# MSXIV_DC-DC_Converter.net
KiCad netlist of a schematic drawn in Altium Designer
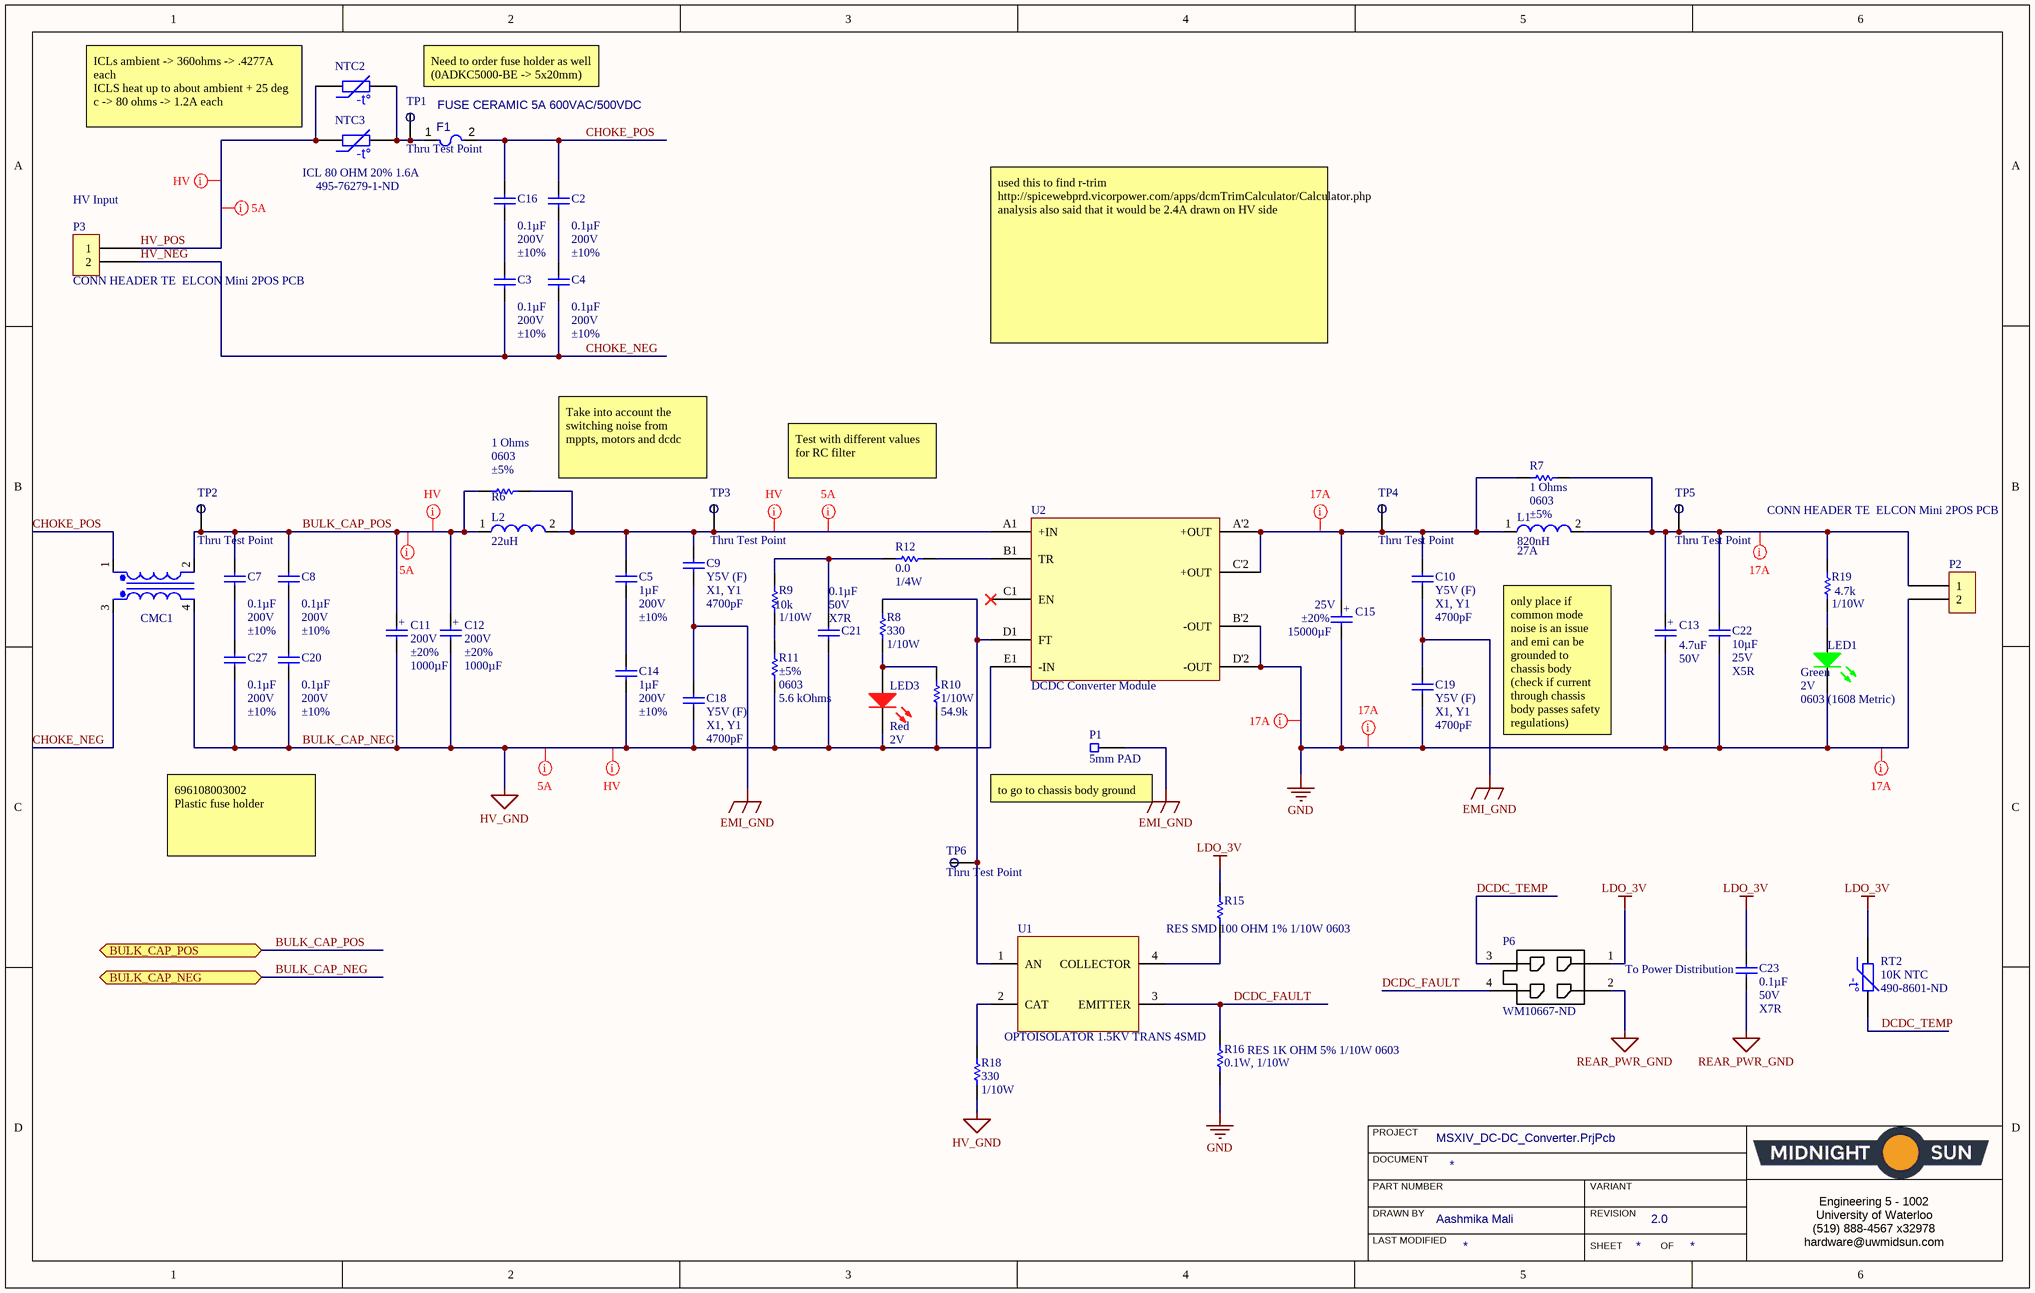
[diagram p0: MSXIV_DC-DC_Converter.SchDoc]

(export (version "E")
  (design (tool "Eeschema 10.0.6"))
  (components
    (comp (ref "C2")
      (value "CAP CER 0.1UF 200V X7R 1206")
      (footprint "CAP, 1206")
      (fields
        (field (name "CAPACITANCE") "0.1µF")
        (field (name "VOLTAGE - RATED") "200V")
        (field (name "TOLERANCE") "±10%")
      )
      (libsource (lib "Schematic Diagrams") (part "CAP CER 0.1UF 200V X7R 1206"))
    )
    (comp (ref "C3")
      (value "CAP CER 0.1UF 200V X7R 1206")
      (footprint "CAP, 1206")
      (fields
        (field (name "CAPACITANCE") "0.1µF")
        (field (name "VOLTAGE - RATED") "200V")
        (field (name "TOLERANCE") "±10%")
      )
      (libsource (lib "Schematic Diagrams") (part "CAP CER 0.1UF 200V X7R 1206"))
    )
    (comp (ref "C4")
      (value "CAP CER 0.1UF 200V X7R 1206")
      (footprint "CAP, 1206")
      (fields
        (field (name "CAPACITANCE") "0.1µF")
        (field (name "VOLTAGE - RATED") "200V")
        (field (name "TOLERANCE") "±10%")
      )
      (libsource (lib "Schematic Diagrams") (part "CAP CER 0.1UF 200V X7R 1206"))
    )
    (comp (ref "C5")
      (value "CAP CER 1UF 200V X7R 2220")
      (footprint "CAP, 2220")
      (description "1µF ±10% 200V Ceramic Capacitor X7R 2220 (5750 Metric)")
      (fields
        (field (name "MANUFACTURER") "Murata Electronics")
        (field (name "CAPACITANCE") "1µF")
        (field (name "VOLTAGE - RATED") "200V")
        (field (name "TOLERANCE") "±10%")
      )
      (libsource (lib "Schematic Diagrams") (part "CAP CER 1UF 200V X7R 2220"))
    )
    (comp (ref "C7")
      (value "CAP CER 0.1UF 200V X7R 1206")
      (footprint "CAP, 1206")
      (fields
        (field (name "CAPACITANCE") "0.1µF")
        (field (name "VOLTAGE - RATED") "200V")
        (field (name "TOLERANCE") "±10%")
      )
      (libsource (lib "Schematic Diagrams") (part "CAP CER 0.1UF 200V X7R 1206"))
    )
    (comp (ref "C8")
      (value "CAP CER 0.1UF 200V X7R 1206")
      (footprint "CAP, 1206")
      (fields
        (field (name "CAPACITANCE") "0.1µF")
        (field (name "VOLTAGE - RATED") "200V")
        (field (name "TOLERANCE") "±10%")
      )
      (libsource (lib "Schematic Diagrams") (part "CAP CER 0.1UF 200V X7R 1206"))
    )
    (comp (ref "C9")
      (value "4700pF")
      (footprint "CAP 4700PF 400VAC Y5V RADIAL")
      (description "4700pF ±20% 400VAC Ceramic Capacitor Y5V (F) Radial, Disc")
      (fields
        (field (name "MANUFACTURER") "KEMET")
        (field (name "MANUFACTURER PART NUMBER") "C951U472MVVDBA7317")
        (field (name "TEMPERATURE COEFFICIENT") "Y5V (F)")
        (field (name "RATINGS") "X1, Y1")
      )
      (libsource (lib "Schematic Diagrams") (part "CAP CER 4700PF 400VAC Y5V RADIAL"))
    )
    (comp (ref "C10")
      (value "4700pF")
      (footprint "CAP 4700PF 400VAC Y5V RADIAL")
      (description "4700pF ±20% 400VAC Ceramic Capacitor Y5V (F) Radial, Disc")
      (fields
        (field (name "MANUFACTURER") "KEMET")
        (field (name "MANUFACTURER PART NUMBER") "C951U472MVVDBA7317")
        (field (name "TEMPERATURE COEFFICIENT") "Y5V (F)")
        (field (name "RATINGS") "X1, Y1")
      )
      (libsource (lib "Schematic Diagrams") (part "CAP CER 4700PF 400VAC Y5V RADIAL"))
    )
    (comp (ref "C11")
      (value "CAP ALUM 1000UF 20% 200V SNAP")
      (footprint "CAP ALUM 1000uF 200V")
      (description "CAP RADIAL ALUM 1000UF 20% 200V SNAP")
      (fields
        (field (name "VOLTAGE - RATED") "200V")
        (field (name "TOLERANCE") "±20%")
        (field (name "CAPACITANCE") "1000µF")
      )
      (libsource (lib "Schematic Diagrams") (part "CAP ALUM 1000UF 20% 200V SNAP"))
    )
    (comp (ref "C12")
      (value "CAP ALUM 1000UF 20% 200V SNAP")
      (footprint "CAP ALUM 1000uF 200V")
      (description "CAP RADIAL ALUM 1000UF 20% 200V SNAP")
      (fields
        (field (name "VOLTAGE - RATED") "200V")
        (field (name "TOLERANCE") "±20%")
        (field (name "CAPACITANCE") "1000µF")
      )
      (libsource (lib "Schematic Diagrams") (part "CAP ALUM 1000UF 20% 200V SNAP"))
    )
    (comp (ref "C13")
      (value "EEE-1HA4R7NP")
      (footprint "CAP ALUM 6.3MM RADIAL SMD")
      (description "4.7µF 50V Aluminum Electrolytic Capacitors Radial, Can - SMD 2000 Hrs @ 85°C")
      (fields
        (field (name "TOLERANCE") "20%")
        (field (name "CAPACITANCE") "4.7uF")
        (field (name "VOLTAGE RATING (DC)") "50V")
      )
      (libsource (lib "Schematic Diagrams") (part "CAP ALUM 4.7UF 20% 50V SMD"))
    )
    (comp (ref "C14")
      (value "CAP CER 1UF 200V X7R 2220")
      (footprint "CAP, 2220")
      (description "1µF ±10% 200V Ceramic Capacitor X7R 2220 (5750 Metric)")
      (fields
        (field (name "MANUFACTURER") "Murata Electronics")
        (field (name "CAPACITANCE") "1µF")
        (field (name "VOLTAGE - RATED") "200V")
        (field (name "TOLERANCE") "±10%")
      )
      (libsource (lib "Schematic Diagrams") (part "CAP CER 1UF 200V X7R 2220"))
    )
    (comp (ref "C15")
      (value "CAP ALUM 15000UF 20% 25V SNAP")
      (footprint "CAP ALUM 1000uF 200V")
      (description "15000µF 25V Aluminum Electrolytic Capacitors Radial, Can - Snap-In 40mOhm 3000 Hrs @ 105°C")
      (fields
        (field (name "VOLTAGE - RATED") "25V")
        (field (name "TOLERANCE") "±20%")
        (field (name "CAPACITANCE") "15000µF")
        (field (name "MANUFACTURER") "Cornell Dubilier Electronics (CDE)")
        (field (name "MANUFACTURER PART NUMBER") "SLP153M025C4P3")
      )
      (libsource (lib "Schematic Diagrams") (part "CAP ALUM 15000UF 20% 25V SNAP"))
    )
    (comp (ref "C16")
      (value "CAP CER 0.1UF 200V X7R 1206")
      (footprint "CAP, 1206")
      (fields
        (field (name "CAPACITANCE") "0.1µF")
        (field (name "VOLTAGE - RATED") "200V")
        (field (name "TOLERANCE") "±10%")
      )
      (libsource (lib "Schematic Diagrams") (part "CAP CER 0.1UF 200V X7R 1206"))
    )
    (comp (ref "C18")
      (value "4700pF")
      (footprint "CAP 4700PF 400VAC Y5V RADIAL")
      (description "4700pF ±20% 400VAC Ceramic Capacitor Y5V (F) Radial, Disc")
      (fields
        (field (name "MANUFACTURER") "KEMET")
        (field (name "MANUFACTURER PART NUMBER") "C951U472MVVDBA7317")
        (field (name "TEMPERATURE COEFFICIENT") "Y5V (F)")
        (field (name "RATINGS") "X1, Y1")
      )
      (libsource (lib "Schematic Diagrams") (part "CAP CER 4700PF 400VAC Y5V RADIAL"))
    )
    (comp (ref "C19")
      (value "4700pF")
      (footprint "CAP 4700PF 400VAC Y5V RADIAL")
      (description "4700pF ±20% 400VAC Ceramic Capacitor Y5V (F) Radial, Disc")
      (fields
        (field (name "MANUFACTURER") "KEMET")
        (field (name "MANUFACTURER PART NUMBER") "C951U472MVVDBA7317")
        (field (name "TEMPERATURE COEFFICIENT") "Y5V (F)")
        (field (name "RATINGS") "X1, Y1")
      )
      (libsource (lib "Schematic Diagrams") (part "CAP CER 4700PF 400VAC Y5V RADIAL"))
    )
    (comp (ref "C20")
      (value "CAP CER 0.1UF 200V X7R 1206")
      (footprint "CAP, 1206")
      (fields
        (field (name "CAPACITANCE") "0.1µF")
        (field (name "VOLTAGE - RATED") "200V")
        (field (name "TOLERANCE") "±10%")
      )
      (libsource (lib "Schematic Diagrams") (part "CAP CER 0.1UF 200V X7R 1206"))
    )
    (comp (ref "C21")
      (value "CAP CER 0.1UF 50V 10% X7R 0603")
      (footprint "CAP, 0603")
      (description "0.10µF ±10% 50V Ceramic Capacitor X7R 0603 (1608 Metric)")
      (fields
        (field (name "TOLERANCE") "±10%")
        (field (name "CAPACITANCE") "0.1µF")
        (field (name "VOLTAGE") "50V")
        (field (name "TEMPERATURE COEFFICIENT") "X7R")
      )
      (libsource (lib "Schematic Diagrams") (part "CAP CER 0.1UF 50V 10% X7R 0603"))
    )
    (comp (ref "C22")
      (value "CAP CER 10uF 25V 20% X5R 0603")
      (footprint "CAP, 0603")
      (description "10µF ±20% 25V Ceramic Capacitor X5R 0603 (1608 Metric)")
      (fields
        (field (name "TOLERANCE") "±20%")
        (field (name "CAPACITANCE") "10µF")
        (field (name "VOLTAGE") "25V")
        (field (name "TEMPERATURE COEFFICIENT") "X5R")
      )
      (libsource (lib "Schematic Diagrams") (part "CAP CER 10uF 25V 20% X5R 0603"))
    )
    (comp (ref "C23")
      (value "CAP CER 0.1UF 50V 10% X7R 0603")
      (footprint "CAP, 0603")
      (description "0.10µF ±10% 50V Ceramic Capacitor X7R 0603 (1608 Metric)")
      (fields
        (field (name "TOLERANCE") "±10%")
        (field (name "CAPACITANCE") "0.1µF")
        (field (name "VOLTAGE") "50V")
        (field (name "TEMPERATURE COEFFICIENT") "X7R")
      )
      (libsource (lib "Schematic Diagrams") (part "CAP CER 0.1UF 50V 10% X7R 0603"))
    )
    (comp (ref "C27")
      (value "CAP CER 0.1UF 200V X7R 1206")
      (footprint "CAP, 1206")
      (fields
        (field (name "CAPACITANCE") "0.1µF")
        (field (name "VOLTAGE - RATED") "200V")
        (field (name "TOLERANCE") "±10%")
      )
      (libsource (lib "Schematic Diagrams") (part "CAP CER 0.1UF 200V X7R 1206"))
    )
    (comp (ref "CMC1")
      (value "CM Choke")
      (footprint "LCCI 50 Common mode choke")
      (description "2 Line Common Mode Choke Surface Mount  5.6A DCR 21mOhm")
      (fields (field (name "PARTNUMBER") "P0353NL"))
      (libsource (lib "Schematic Diagrams") (part "COMMON MODE CHOKE 5.6A 2LN SMD"))
    )
    (comp (ref "F1")
      (value "FUSE CERAMIC 5A 600VAC/500VDC")
      (footprint "0ADKC5000-BE-Footprint-1")
      (description "FUSE CERAMIC 5A 600VAC/500VDC FOOTPRINT IS FOR 5x20mm HOLDER")
      (libsource (lib "University of Waterloo - Solar Car Team") (part "FUSE-2"))
    )
    (comp (ref "L1")
      (value "FIXED IND 820NH 27A 0.9 MOHM SMD")
      (footprint "WE-HCI-1365")
      (fields
        (field (name "INDUCTANCE") "820nH")
        (field (name "CURRENT RATING") "27A")
        (field (name "TOLERANCE") "20%")
      )
      (libsource (lib "University of Waterloo - Solar Car Team") (part "PAS-IND-INDUCTOR-2"))
    )
    (comp (ref "L2")
      (value "FIXED IND 22UH 5.3A 28 MOHM SMD")
      (footprint "WE-PD-XXL")
      (description "Inductor, SMD 22 uH 5.3 A ±20%, 7447709220, Würth Elektronik")
      (fields (field (name "INDUCTANCE") "22uH") (field (name "TOLERANCE") "20%"))
      (libsource (lib "University of Waterloo - Solar Car Team") (part "PAS-IND-INDUCTOR-2"))
    )
    (comp (ref "LED1")
      (value "LED GREEN CLEAR 2V 0603")
      (footprint "LED_0603")
      (description "Green 572nm LED Indication - Discrete 2V 0603 (1608 Metric)")
      (fields
        (field (name "MANUFACTURER") "Wurth Electronics Inc.")
        (field (name "MANUFACTURER PART NUMBER") "150060VS75000")
        (field (name "PACKAGE / CASE") "0603 (1608 Metric)")
        (field (name "COLOR") "Green")
        (field (name "VOLTAGE - FORWARD (VF) (TYP)") "2V")
      )
      (libsource (lib "Schematic Diagrams") (part "LED GREEN CLEAR 2V 0603"))
    )
    (comp (ref "LED3")
      (value "LED RED CLEAR 2V 0603")
      (footprint "LED_0603")
      (description "Red 631nm LED Indication - Discrete 2V 0603 (1608 Metric)")
      (fields
        (field (name "COLOR") "Red")
        (field (name "VOLTAGE - FORWARD (VF) (TYP)") "2V")
        (field (name "MANUFACTURER") "Wurth Electronics Inc.")
        (field (name "MANUFACTURER PART NUMBER") "150060RS75000")
        (field (name "SOURCE") "Schematic Diagrams.SchLib")
      )
      (libsource (lib "University of Waterloo - Solar Car Team") (part "LED RED CLEAR 2V 0603"))
    )
    (comp (ref "NTC2")
      (value "ICL 80 OHM 20% 1.6A")
      (footprint "ICL_THROUGH_HOLE_B57236S0800M051")
      (description "Thermistor NTC 80 Ohm 20% 2-Pin Radial 3300K Cardboard T/R")
      (fields
        (field (name "MANUFACTURER") "TDK EPCOS")
        (field (name "MANUFACTURER PART NUMBER") "B57236S0800M051")
      )
      (libsource (lib "Schematic Diagrams") (part "ICL 80 OHM 20% 1.6A"))
    )
    (comp (ref "NTC3")
      (value "ICL 80 OHM 20% 1.6A")
      (footprint "ICL_THROUGH_HOLE_B57236S0800M051")
      (description "Thermistor NTC 80 Ohm 20% 2-Pin Radial 3300K Cardboard T/R")
      (fields
        (field (name "MANUFACTURER") "TDK EPCOS")
        (field (name "MANUFACTURER PART NUMBER") "B57236S0800M051")
        (field (name "SUPPLIER PART NUMBER 1") "495-76279-1-ND")
      )
      (libsource (lib "Schematic Diagrams") (part "ICL 80 OHM 20% 1.6A"))
    )
    (comp (ref "P1")
      (value "5mm PAD")
      (footprint "5mm PAD")
      (description "5x5mm pad to solder 16 gauge wire")
      (libsource (lib "Schematic Diagrams") (part "5mm PAD"))
    )
    (comp (ref "P2")
      (value "CONN HEADER TE  ELCON Mini 2POS PCB")
      (footprint "CONN HEADER TE  ELCON Mini 2POS PCB-Footprint-1")
      (description "CONN HEADER 2POS PCB")
      (libsource (lib "University of Waterloo - Solar Car Team") (part "CONN HEADER TE  ELCON Mini 2POS PCB"))
    )
    (comp (ref "P3")
      (value "CONN HEADER TE  ELCON Mini 2POS PCB")
      (footprint "CONN HEADER TE  ELCON Mini 2POS PCB-Footprint-1")
      (description "CONN HEADER 2POS PCB")
      (libsource (lib "") (part "CONN HEADER TE  ELCON Mini 2POS PCB_1"))
    )
    (comp (ref "P6")
      (value "CONN 4POS MICRO-FIT 3mm")
      (footprint "CONN 4POS MICROFIT (2x2)")
      (fields
        (field (name "MANUFACTURER") "Molex, LLC")
        (field (name "MANUFACTURER PART NUMBER") "0430450827")
        (field (name "SUPPLIER PART NUMBER 1") "WM10667-ND")
      )
      (libsource (lib "Schematic Diagrams") (part "CONN 4POS MICRO-FIT 3mm"))
    )
    (comp (ref "R6")
      (value "RES 1 OHM 5% 1/10W 0603")
      (footprint "RES, 0603")
      (description "RES SMD 1 OHM 5% 1/10W 0603")
      (fields
        (field (name "DIGI-KEY PART NUMBER") "RHM1.0AZCT-ND")
        (field (name "RESISTANCE") "1 Ohms")
        (field (name "SUPPLIER DEVICE PACKAGE") "0603")
        (field (name "TOLERANCE") "±5%")
      )
      (libsource (lib "Schematic Diagrams") (part "RES 1 OHM 5% 1/10W 0603"))
    )
    (comp (ref "R7")
      (value "RES 1 OHM 5% 1/10W 0603")
      (footprint "RES, 0603")
      (description "RES SMD 1 OHM 5% 1/10W 0603")
      (fields
        (field (name "DIGI-KEY PART NUMBER") "RHM1.0AZCT-ND")
        (field (name "RESISTANCE") "1 Ohms")
        (field (name "SUPPLIER DEVICE PACKAGE") "0603")
        (field (name "TOLERANCE") "±5%")
      )
      (libsource (lib "Schematic Diagrams") (part "RES 1 OHM 5% 1/10W 0603"))
    )
    (comp (ref "R8")
      (value "RES 330 OHM 1% 1/10W 0603")
      (footprint "RES, 0603")
      (fields
        (field (name "MANUFACTURER") "TE Connectivity")
        (field (name "MANUFACTURER PART NUMBER") "1-2176339-9")
        (field (name "RESISTANCE") "330")
        (field (name "POWER") "1/10W")
      )
      (libsource (lib "Schematic Diagrams") (part "RES 330 OHM 1% 1/10W 0603"))
    )
    (comp (ref "R9")
      (value "RES 10K OHM 1% 1/10W 0603")
      (footprint "RES, 0603")
      (description "RES SMD 10K OHM 1% 1/10W 0603")
      (fields
        (field (name "TOLERANCE") "±1%")
        (field (name "RESISTANCE") "10k")
        (field (name "POWER") "1/10W")
      )
      (libsource (lib "Schematic Diagrams") (part "RES 10K OHM 1% 1/10W 0603"))
    )
    (comp (ref "R10")
      (value "RES 54.9K OHM 1% 1/10W 0603")
      (footprint "RES, 0603")
      (description "54.9k Ohm ±1% 0.1W, 1/10W Chip Resistor 0603 (1608 Metric) Automotive AEC-Q200 Thick Film")
      (fields
        (field (name "MANUFACTURER") "Panasonic Electronic Components")
        (field (name "MANUFACTURER PART NUMBER") "ERJ-3EKF5492V")
        (field (name "POWER (WATTS)") "1/10W")
        (field (name "RESISTANCE (OHMS)") "54.9k")
      )
      (libsource (lib "Schematic Diagrams") (part "RES 54.9K OHM 1% 1/10W 0603"))
    )
    (comp (ref "R11")
      (value "RES 15.6K OHM 0.1% 1/10W 0402")
      (footprint "RES, 0603")
      (description "5.6 kOhms ±5% 0.1W, 1/10W Chip Resistor 0603 (1608 Metric) Moisture Resistant Thick Film")
      (fields
        (field (name "TOLERANCE") "±5%")
        (field (name "SUPPLIER DEVICE PACKAGE") "0603")
        (field (name "RESISTANCE") "5.6 kOhms")
      )
      (libsource (lib "Schematic Diagrams") (part "RES 5.6K OHM 5% 1/10W 0603"))
    )
    (comp (ref "R12")
      (value "RES 0.0 OHM 1/4W 0603")
      (footprint "RES, 0603")
      (description "RES SMD 0.0 OHM JUMPER 1/4W 0603")
      (fields (field (name "RESISTANCE") "0.0") (field (name "POWER (WATTS)") "1/4W"))
      (libsource (lib "Schematic Diagrams") (part "RES 0.0 OHM 1/4W 0603"))
    )
    (comp (ref "R15")
      (value "RES SMD 100 OHM 1% 1/10W 0603")
      (footprint "RESC1608X55X25NL10T15")
      (description "YAGEO         RC0603FR-07100RL            RES, THICK FILM, 100R, 1%, 0.1W, 0603, REEL")
      (fields (field (name "TOLERANCE") "1%"))
      (libsource (lib "University of Waterloo - Solar Car Team") (part "RES-2"))
    )
    (comp (ref "R16")
      (value "RES 1K OHM 5% 1/10W 0603")
      (footprint "RES, 0603")
      (description "1k Ohm ±5% 0.1W, 1/10W Chip Resistor 0603 (1608 Metric)")
      (fields
        (field (name "TOLERANCE") "5%")
        (field (name "MANUFACTURER") "Yageo")
        (field (name "POWER (WATTS)") "0.1W, 1/10W")
        (field (name "SOURCE") "Schematic Diagrams.SchLib")
      )
      (libsource (lib "University of Waterloo - Solar Car Team") (part "Symbol"))
    )
    (comp (ref "R18")
      (value "RES 330 OHM 1% 1/10W 0603")
      (footprint "RES, 0603")
      (fields
        (field (name "MANUFACTURER") "TE Connectivity")
        (field (name "MANUFACTURER PART NUMBER") "1-2176339-9")
        (field (name "RESISTANCE") "330")
        (field (name "POWER") "1/10W")
      )
      (libsource (lib "Schematic Diagrams") (part "RES 330 OHM 1% 1/10W 0603"))
    )
    (comp (ref "R19")
      (value "RES 4.7K OHM 1% 1/10W 0603")
      (footprint "RES, 0603")
      (description "4.7k Ohm ±1% 0.1W, 1/10W Chip Resistor 0603 (1608 Metric) Moisture Resistant Thick Film")
      (fields
        (field (name "TOLERANCE") "±1%")
        (field (name "RESISTANCE (OHMS)") "4.7k")
        (field (name "POWER (WATTS)") "1/10W")
      )
      (libsource (lib "Schematic Diagrams") (part "RES 4.7K OHM 1% 1/10W 0603"))
    )
    (comp (ref "RT2")
      (value "10K NTC")
      (footprint "NTC THERMISTOR BEAD")
      (description "NTC Thermistor 10k Bead")
      (fields
        (field (name "MANUFACTURER") "Murata Electronics North America")
        (field (name "MANUFACTURER PART NUMBER") "NXRT15XH103FA1B030")
        (field (name "SUPPLIER PART NUMBER 1") "490-8601-ND")
      )
      (libsource (lib "Schematic Diagrams") (part "NTC THERMISTOR 10K 1% BEAD"))
    )
    (comp (ref "TP1")
      (value "Thru Test Point")
      (footprint "Thru Test Point")
      (fields (field (name "SOURCE") "Schematic Diagrams.SchLib"))
      (libsource (lib "University of Waterloo - Solar Car Team") (part "Thru Test Point"))
    )
    (comp (ref "TP2")
      (value "Thru Test Point")
      (footprint "Thru Test Point")
      (fields (field (name "SOURCE") "Schematic Diagrams.SchLib"))
      (libsource (lib "University of Waterloo - Solar Car Team") (part "Thru Test Point"))
    )
    (comp (ref "TP3")
      (value "Thru Test Point")
      (footprint "Thru Test Point")
      (fields (field (name "SOURCE") "Schematic Diagrams.SchLib"))
      (libsource (lib "University of Waterloo - Solar Car Team") (part "Thru Test Point"))
    )
    (comp (ref "TP4")
      (value "Thru Test Point")
      (footprint "Thru Test Point")
      (fields (field (name "SOURCE") "Schematic Diagrams.SchLib"))
      (libsource (lib "University of Waterloo - Solar Car Team") (part "Thru Test Point"))
    )
    (comp (ref "TP5")
      (value "Thru Test Point")
      (footprint "Thru Test Point")
      (fields (field (name "SOURCE") "Schematic Diagrams.SchLib"))
      (libsource (lib "University of Waterloo - Solar Car Team") (part "Thru Test Point"))
    )
    (comp (ref "TP6")
      (value "Thru Test Point")
      (footprint "Thru Test Point")
      (fields (field (name "SOURCE") "Schematic Diagrams.SchLib"))
      (libsource (lib "University of Waterloo - Solar Car Team") (part "Thru Test Point"))
    )
    (comp (ref "U1")
      (value "OPTOISOLATOR 1.5KV TRANS 4SMD")
      (footprint "SOIC127P610X228-4N")
      (description "Transistor Output Optocouplers Dual 1 Form-A relay 4-Pin SOP")
      (libsource (lib "University of Waterloo - Solar Car Team") (part "CPC1001N"))
    )
    (comp (ref "U2")
      (value "DCDC VICOR CONVERTER 15V 240W - DCM3623TA5N17B4T70")
      (footprint "IC, DCDC converter DCM3623TA5N17B4T70")
      (description "DC DC CONVERTER 15V 240W")
      (fields (field (name "POWER") "240W") (field (name "TYPE") "DCDC Converter Module"))
      (libsource (lib "Schematic Diagrams") (part "DCDC VICOR CONVERTER 15V 240W - DCM3623TA5N17B4T70"))
    )
  )
  (nets
    (net (code "1") (name "/BULK_CAP_POS") (class "Default")
      (node (ref "C11") (pin "1") (pinfunction "1_1") (pintype "passive"))
      (node (ref "C12") (pin "1") (pinfunction "1_1") (pintype "passive"))
      (node (ref "C7") (pin "1") (pinfunction "1_1") (pintype "passive"))
      (node (ref "C8") (pin "1") (pinfunction "1_1") (pintype "passive"))
      (node (ref "CMC1") (pin "2") (pintype "passive"))
      (node (ref "L2") (pin "1") (pinfunction "1_1") (pintype "passive"))
      (node (ref "R6") (pin "1") (pinfunction "1_1") (pintype "passive"))
      (node (ref "TP2") (pin "TH_TP") (pinfunction "1_TH_TP") (pintype "passive"))
    )
    (net (code "2") (name "/CHOKE_NEG") (class "Default")
      (node (ref "C3") (pin "2") (pinfunction "2_2") (pintype "passive"))
      (node (ref "C4") (pin "2") (pinfunction "2_2") (pintype "passive"))
      (node (ref "CMC1") (pin "3") (pintype "passive"))
      (node (ref "P3") (pin "2") (pinfunction "2_2") (pintype "passive"))
    )
    (net (code "3") (name "/CHOKE_POS") (class "Default")
      (node (ref "C16") (pin "1") (pinfunction "1_1") (pintype "passive"))
      (node (ref "C2") (pin "1") (pinfunction "1_1") (pintype "passive"))
      (node (ref "CMC1") (pin "1") (pintype "passive"))
      (node (ref "F1") (pin "2") (pinfunction "2_2") (pintype "passive"))
    )
    (net (code "4") (name "/DCDC_FAULT") (class "Default")
      (node (ref "P6") (pin "4") (pinfunction "4_4") (pintype "passive"))
      (node (ref "R16") (pin "1") (pinfunction "1_1") (pintype "passive"))
      (node (ref "U1") (pin "3") (pinfunction "EMITTER_3") (pintype "passive"))
    )
    (net (code "5") (name "/DCDC_TEMP") (class "Default")
      (node (ref "P6") (pin "3") (pinfunction "3_3") (pintype "passive"))
      (node (ref "RT2") (pin "2") (pinfunction "2_2") (pintype "passive"))
    )
    (net (code "6") (name "/HV_POS") (class "Default")
      (node (ref "NTC2") (pin "1") (pinfunction "1_1") (pintype "passive"))
      (node (ref "NTC3") (pin "1") (pinfunction "1_1") (pintype "passive"))
      (node (ref "P3") (pin "1") (pinfunction "1_1") (pintype "passive"))
    )
    (net (code "7") (name "EMI_GND") (class "Default")
      (node (ref "C10") (pin "2") (pinfunction "2_2") (pintype "passive"))
      (node (ref "C18") (pin "1") (pinfunction "1_1") (pintype "passive"))
      (node (ref "C19") (pin "1") (pinfunction "1_1") (pintype "passive"))
      (node (ref "C9") (pin "2") (pinfunction "2_2") (pintype "passive"))
      (node (ref "P1") (pin "1") (pinfunction "1_1") (pintype "passive"))
    )
    (net (code "8") (name "GND") (class "Default")
      (node (ref "C13") (pin "2") (pinfunction "2_2") (pintype "passive"))
      (node (ref "C15") (pin "2") (pinfunction "2_2") (pintype "passive"))
      (node (ref "C19") (pin "2") (pinfunction "2_2") (pintype "passive"))
      (node (ref "C22") (pin "2") (pinfunction "2_2") (pintype "passive"))
      (node (ref "LED1") (pin "2") (pinfunction "K_2") (pintype "passive"))
      (node (ref "P2") (pin "2") (pinfunction "2_2") (pintype "passive"))
      (node (ref "R16") (pin "2") (pinfunction "2_2") (pintype "passive"))
      (node (ref "U2") (pin "B'2") (pinfunction "-OUT_B'2") (pintype "passive"))
      (node (ref "U2") (pin "D'2") (pinfunction "-OUT_D'2") (pintype "passive"))
    )
    (net (code "9") (name "HV_GND") (class "Default")
      (node (ref "C11") (pin "2") (pinfunction "2_2") (pintype "passive"))
      (node (ref "C12") (pin "2") (pinfunction "2_2") (pintype "passive"))
      (node (ref "C14") (pin "2") (pinfunction "2_2") (pintype "passive"))
      (node (ref "C18") (pin "2") (pinfunction "2_2") (pintype "passive"))
      (node (ref "C20") (pin "2") (pinfunction "2_2") (pintype "passive"))
      (node (ref "C21") (pin "2") (pinfunction "2_2") (pintype "passive"))
      (node (ref "C27") (pin "2") (pinfunction "2_2") (pintype "passive"))
      (node (ref "CMC1") (pin "4") (pintype "passive"))
      (node (ref "LED3") (pin "2") (pinfunction "K_2") (pintype "passive"))
      (node (ref "R10") (pin "2") (pinfunction "2_2") (pintype "passive"))
      (node (ref "R11") (pin "1") (pinfunction "1_1") (pintype "passive"))
      (node (ref "R18") (pin "2") (pinfunction "2_2") (pintype "passive"))
      (node (ref "U2") (pin "E1") (pinfunction "-IN_E1") (pintype "passive"))
    )
    (net (code "10") (name "LDO_3V") (class "Default")
      (node (ref "C23") (pin "1") (pinfunction "1_1") (pintype "passive"))
      (node (ref "P6") (pin "1") (pinfunction "1_1") (pintype "passive"))
      (node (ref "R15") (pin "2") (pinfunction "2_2") (pintype "passive"))
      (node (ref "RT2") (pin "1") (pinfunction "1_1") (pintype "passive"))
    )
    (net (code "11") (name "Net-(C2-Pad2)") (class "Default")
      (node (ref "C2") (pin "2") (pinfunction "2_2") (pintype "passive"))
      (node (ref "C4") (pin "1") (pinfunction "1_1") (pintype "passive"))
    )
    (net (code "12") (name "Net-(C14-Pad1)") (class "Default")
      (node (ref "C14") (pin "1") (pinfunction "1_1") (pintype "passive"))
      (node (ref "C5") (pin "2") (pinfunction "2_2") (pintype "passive"))
    )
    (net (code "13") (name "Net-(C16-Pad2)") (class "Default")
      (node (ref "C16") (pin "2") (pinfunction "2_2") (pintype "passive"))
      (node (ref "C3") (pin "1") (pinfunction "1_1") (pintype "passive"))
    )
    (net (code "14") (name "Net-(C20-Pad1)") (class "Default")
      (node (ref "C20") (pin "1") (pinfunction "1_1") (pintype "passive"))
      (node (ref "C8") (pin "2") (pinfunction "2_2") (pintype "passive"))
    )
    (net (code "15") (name "Net-(C21-Pad1)") (class "Default")
      (node (ref "C21") (pin "1") (pinfunction "1_1") (pintype "passive"))
      (node (ref "R12") (pin "1") (pinfunction "1_1") (pintype "passive"))
      (node (ref "R9") (pin "1") (pinfunction "1_1") (pintype "passive"))
    )
    (net (code "16") (name "Net-(C27-Pad1)") (class "Default")
      (node (ref "C27") (pin "1") (pinfunction "1_1") (pintype "passive"))
      (node (ref "C7") (pin "2") (pinfunction "2_2") (pintype "passive"))
    )
    (net (code "17") (name "Net-(LED1-A)") (class "Default")
      (node (ref "LED1") (pin "1") (pinfunction "A_1") (pintype "passive"))
      (node (ref "R19") (pin "2") (pinfunction "2_2") (pintype "passive"))
    )
    (net (code "18") (name "Net-(LED3-A)") (class "Default")
      (node (ref "LED3") (pin "1") (pinfunction "A_1") (pintype "passive"))
      (node (ref "R10") (pin "1") (pinfunction "1_1") (pintype "passive"))
      (node (ref "R8") (pin "2") (pinfunction "2_2") (pintype "passive"))
    )
    (net (code "19") (name "Net-(R11-Pad2)") (class "Default")
      (node (ref "R11") (pin "2") (pinfunction "2_2") (pintype "passive"))
      (node (ref "R9") (pin "2") (pinfunction "2_2") (pintype "passive"))
    )
    (net (code "20") (name "Net-(TP1-1)") (class "Default")
      (node (ref "F1") (pin "1") (pinfunction "1_1") (pintype "passive"))
      (node (ref "NTC2") (pin "2") (pinfunction "2_2") (pintype "passive"))
      (node (ref "NTC3") (pin "2") (pinfunction "2_2") (pintype "passive"))
      (node (ref "TP1") (pin "TH_TP") (pinfunction "1_TH_TP") (pintype "passive"))
    )
    (net (code "21") (name "Net-(TP3-1)") (class "Default")
      (node (ref "C5") (pin "1") (pinfunction "1_1") (pintype "passive"))
      (node (ref "C9") (pin "1") (pinfunction "1_1") (pintype "passive"))
      (node (ref "L2") (pin "2") (pinfunction "2_2") (pintype "passive"))
      (node (ref "R6") (pin "2") (pinfunction "2_2") (pintype "passive"))
      (node (ref "TP3") (pin "TH_TP") (pinfunction "1_TH_TP") (pintype "passive"))
      (node (ref "U2") (pin "A1") (pinfunction "+IN_A1") (pintype "passive"))
    )
    (net (code "22") (name "Net-(TP4-1)") (class "Default")
      (node (ref "C10") (pin "1") (pinfunction "1_1") (pintype "passive"))
      (node (ref "C15") (pin "1") (pinfunction "1_1") (pintype "passive"))
      (node (ref "L1") (pin "1") (pinfunction "1_1") (pintype "passive"))
      (node (ref "R7") (pin "1") (pinfunction "1_1") (pintype "passive"))
      (node (ref "TP4") (pin "TH_TP") (pinfunction "1_TH_TP") (pintype "passive"))
      (node (ref "U2") (pin "A'2") (pinfunction "+OUT_A'2") (pintype "passive"))
      (node (ref "U2") (pin "C'2") (pinfunction "+OUT_C'2") (pintype "passive"))
    )
    (net (code "23") (name "Net-(TP5-1)") (class "Default")
      (node (ref "C13") (pin "1") (pinfunction "1_1") (pintype "passive"))
      (node (ref "C22") (pin "1") (pinfunction "1_1") (pintype "passive"))
      (node (ref "L1") (pin "2") (pinfunction "2_2") (pintype "passive"))
      (node (ref "P2") (pin "1") (pinfunction "1_1") (pintype "passive"))
      (node (ref "R19") (pin "1") (pinfunction "1_1") (pintype "passive"))
      (node (ref "R7") (pin "2") (pinfunction "2_2") (pintype "passive"))
      (node (ref "TP5") (pin "TH_TP") (pinfunction "1_TH_TP") (pintype "passive"))
    )
    (net (code "24") (name "Net-(TP6-1)") (class "Default")
      (node (ref "R8") (pin "1") (pinfunction "1_1") (pintype "passive"))
      (node (ref "TP6") (pin "TH_TP") (pinfunction "1_TH_TP") (pintype "passive"))
      (node (ref "U1") (pin "1") (pinfunction "AN_1") (pintype "passive"))
      (node (ref "U2") (pin "D1") (pinfunction "FT_D1") (pintype "passive"))
    )
    (net (code "25") (name "Net-(U1-CAT)") (class "Default")
      (node (ref "R18") (pin "1") (pinfunction "1_1") (pintype "passive"))
      (node (ref "U1") (pin "2") (pinfunction "CAT_2") (pintype "passive"))
    )
    (net (code "26") (name "Net-(U1-COLLECTOR)") (class "Default")
      (node (ref "R15") (pin "1") (pinfunction "1_1") (pintype "passive"))
      (node (ref "U1") (pin "4") (pinfunction "COLLECTOR_4") (pintype "passive"))
    )
    (net (code "27") (name "Net-(U2-TR)") (class "Default")
      (node (ref "R12") (pin "2") (pinfunction "2_2") (pintype "passive"))
      (node (ref "U2") (pin "B1") (pinfunction "TR_B1") (pintype "passive"))
    )
    (net (code "28") (name "REAR_PWR_GND") (class "Default")
      (node (ref "C23") (pin "2") (pinfunction "2_2") (pintype "passive"))
      (node (ref "P6") (pin "2") (pinfunction "2_2") (pintype "passive"))
    )
    (net (code "29") (name "unconnected-(U2-EN-PadC1)") (class "Default")
      (node (ref "U2") (pin "C1") (pinfunction "EN_C1") (pintype "passive+no_connect"))
    )
  )
)
